# rys_PCB.net
KiCad netlist of a schematic drawn in Altium Designer
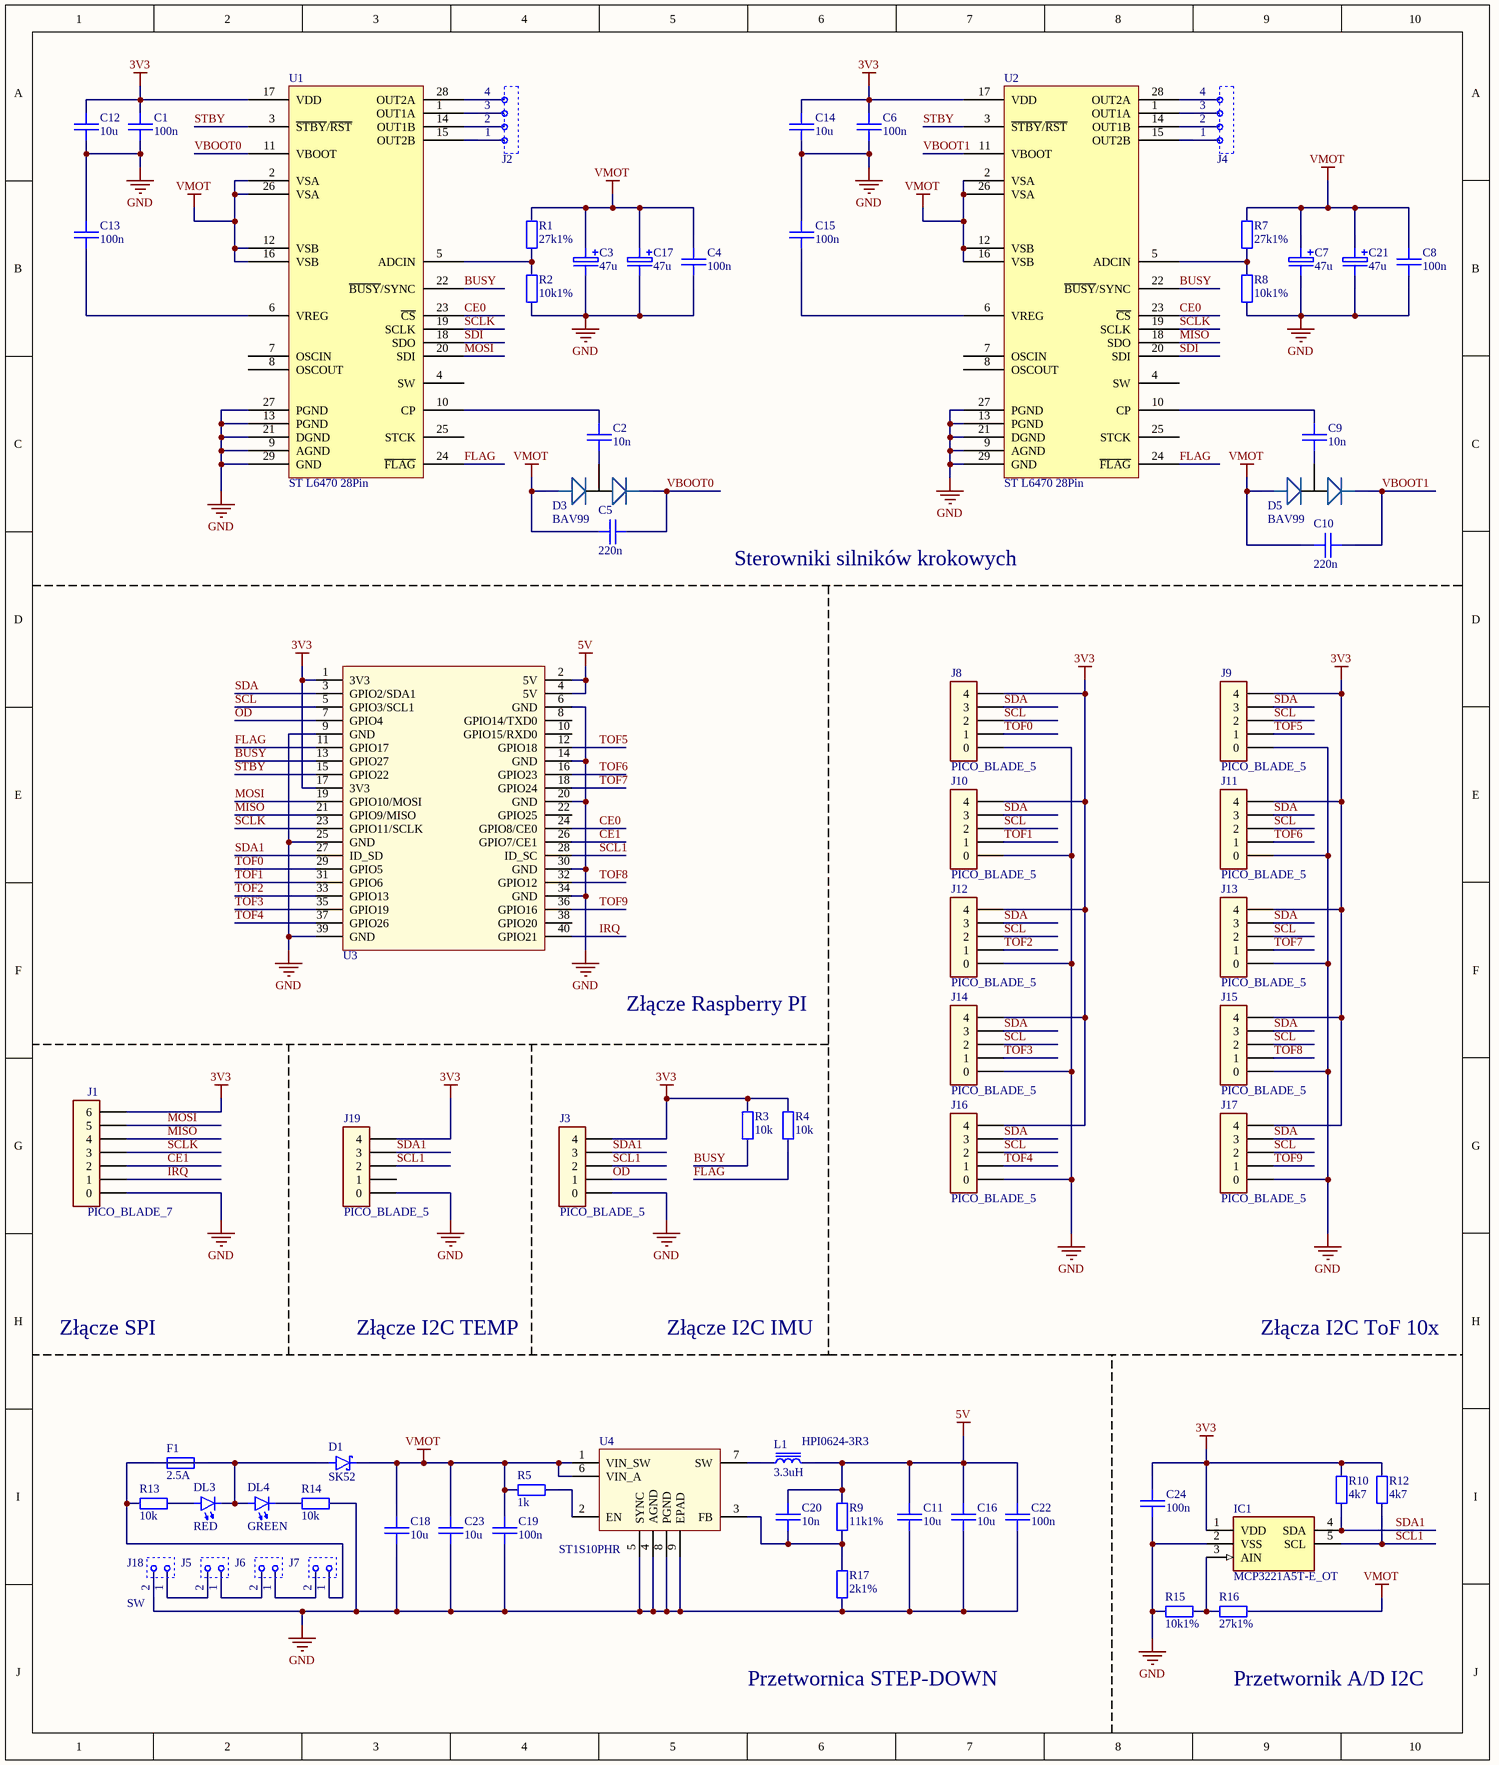
[diagram p0: rys_PCB.SchDoc]

(export (version "E")
  (design (tool "Eeschema 10.0.6"))
  (components
    (comp (ref "C1")
      (value "100n")
      (footprint "Other-Discrete:0603")
      (description "Ceramic Capacitor")
      (libsource (lib "Disc-Other") (part "C_CER"))
    )
    (comp (ref "C2")
      (value "10n")
      (footprint "Other-Discrete:0603")
      (description "Ceramic Capacitor")
      (libsource (lib "Disc-Other") (part "C_CER"))
    )
    (comp (ref "C3")
      (value "47u")
      (footprint "_C_TAN_D")
      (description "Tantalum Capacitor")
      (libsource (lib "Disc-Other") (part "C_TAN"))
    )
    (comp (ref "C4")
      (value "100n")
      (footprint "Other-Discrete:0603")
      (description "Ceramic Capacitor")
      (libsource (lib "Disc-Other") (part "C_CER"))
    )
    (comp (ref "C5")
      (value "220n")
      (footprint "Other-Discrete:0805")
      (description "Ceramic Capacitor")
      (libsource (lib "Disc-Other") (part "C_CER"))
    )
    (comp (ref "C6")
      (value "100n")
      (footprint "Other-Discrete:0603")
      (description "Ceramic Capacitor")
      (libsource (lib "Disc-Other") (part "C_CER"))
    )
    (comp (ref "C7")
      (value "47u")
      (footprint "_C_TAN_D")
      (description "Tantalum Capacitor")
      (libsource (lib "Disc-Other") (part "C_TAN"))
    )
    (comp (ref "C8")
      (value "100n")
      (footprint "Other-Discrete:0603")
      (description "Ceramic Capacitor")
      (libsource (lib "Disc-Other") (part "C_CER"))
    )
    (comp (ref "C9")
      (value "10n")
      (footprint "Other-Discrete:0603")
      (description "Ceramic Capacitor")
      (libsource (lib "Disc-Other") (part "C_CER"))
    )
    (comp (ref "C10")
      (value "220n")
      (footprint "Other-Discrete:0805")
      (description "Ceramic Capacitor")
      (libsource (lib "Disc-Other") (part "C_CER"))
    )
    (comp (ref "C11")
      (value "10u")
      (footprint "Other-Discrete:1210_C")
      (description "Ceramic Capacitor")
      (libsource (lib "Disc-Other") (part "C_CER"))
    )
    (comp (ref "C12")
      (value "10u")
      (footprint "Other-Discrete:1206_C")
      (description "Ceramic Capacitor")
      (libsource (lib "Disc-Other") (part "C_CER"))
    )
    (comp (ref "C13")
      (value "100n")
      (footprint "Other-Discrete:0603")
      (description "Ceramic Capacitor")
      (libsource (lib "Disc-Other") (part "C_CER"))
    )
    (comp (ref "C14")
      (value "10u")
      (footprint "Other-Discrete:1206_C")
      (description "Ceramic Capacitor")
      (libsource (lib "Disc-Other") (part "C_CER"))
    )
    (comp (ref "C15")
      (value "100n")
      (footprint "Other-Discrete:0603")
      (description "Ceramic Capacitor")
      (libsource (lib "Disc-Other") (part "C_CER"))
    )
    (comp (ref "C16")
      (value "10u")
      (footprint "Other-Discrete:1210_C")
      (description "Ceramic Capacitor")
      (libsource (lib "Disc-Other") (part "C_CER"))
    )
    (comp (ref "C17")
      (value "47u")
      (footprint "_C_TAN_D")
      (description "Tantalum Capacitor")
      (libsource (lib "Disc-Other") (part "C_TAN"))
    )
    (comp (ref "C18")
      (value "10u")
      (footprint "Other-Discrete:1210_C")
      (description "Ceramic Capacitor")
      (libsource (lib "Disc-Other") (part "C_CER"))
    )
    (comp (ref "C19")
      (value "100n")
      (footprint "Other-Discrete:0805")
      (description "Ceramic Capacitor")
      (libsource (lib "Disc-Other") (part "C_CER"))
    )
    (comp (ref "C20")
      (value "10n")
      (footprint "Other-Discrete:0603")
      (description "Ceramic Capacitor")
      (libsource (lib "Disc-Other") (part "C_CER"))
    )
    (comp (ref "C21")
      (value "47u")
      (footprint "_C_TAN_D")
      (description "Tantalum Capacitor")
      (libsource (lib "Disc-Other") (part "C_TAN"))
    )
    (comp (ref "C22")
      (value "100n")
      (footprint "Other-Discrete:0805")
      (description "Ceramic Capacitor")
      (libsource (lib "Disc-Other") (part "C_CER"))
    )
    (comp (ref "C23")
      (value "10u")
      (footprint "Other-Discrete:1210_C")
      (description "Ceramic Capacitor")
      (libsource (lib "Disc-Other") (part "C_CER"))
    )
    (comp (ref "C24")
      (value "100n")
      (footprint "Other-Discrete:0603")
      (description "Ceramic Capacitor")
      (libsource (lib "Disc-Other") (part "C_CER"))
    )
    (comp (ref "D1")
      (value "SK52")
      (footprint "SMB/DO-214AA")
      (description "Schottky Diode 2A 60V")
      (libsource (lib "Disc-Diodes") (part "SK26"))
    )
    (comp (ref "D3")
      (value "BAV99")
      (footprint "SOT-23")
      (description "Charge pump diode")
      (libsource (lib "rys_component_lib") (part "BAV99"))
    )
    (comp (ref "D5")
      (value "BAV99")
      (footprint "SOT-23")
      (description "Charge pump diode")
      (libsource (lib "rys_component_lib") (part "BAV99"))
    )
    (comp (ref "DL3")
      (value "RED")
      (footprint "Other-Discrete:0805_LED")
      (description "Light Emitting Diode")
      (libsource (lib "Disc-Opto") (part "LED1"))
    )
    (comp (ref "DL4")
      (value "GREEN")
      (footprint "Other-Discrete:0805_LED")
      (description "Light Emitting Diode")
      (libsource (lib "Disc-Opto") (part "LED1"))
    )
    (comp (ref "F1")
      (value "2.5A")
      (footprint "1206_R")
      (description "Fuse")
      (libsource (lib "rys_component_lib") (part "F"))
    )
    (comp (ref "IC1")
      (value "MCP3221A5T-E_OT")
      (footprint "SamacSys:SOT95P280X145-5N")
      (description "Integrated Circuit")
      (fields
        (field (name "MANUFACTURER_PART_NUMBER") "MCP3221A5T-E/OT")
        (field (name "MOUSER PART NUMBER") "579-MCP3221A5T-E/OT")
      )
      (libsource (lib "*") (part "MCP3221A5T-E_OT"))
    )
    (comp (ref "J1")
      (value "PICO_BLADE_7")
      (footprint "PicoBlade_THT_1x7_HEADER")
      (description "1x7 header")
      (libsource (lib "rys_component_lib") (part "PICO_BLADE_7"))
    )
    (comp (ref "J2")
      (value "Molex Microfit")
      (footprint "MICROFIT 4x1 Vertical")
      (libsource (lib "rys_component_lib") (part "Microfit 1x4"))
    )
    (comp (ref "J3")
      (value "PICO_BLADE_5")
      (footprint "PicoBlade_THT_1x5_HEADER")
      (description "1x5 header")
      (libsource (lib "rys_component_lib") (part "PICO_BLADE_5"))
    )
    (comp (ref "J4")
      (value "Molex Microfit")
      (footprint "MICROFIT 4x1 Vertical")
      (libsource (lib "rys_component_lib") (part "Microfit 1x4"))
    )
    (comp (ref "J5")
      (value "Molex Microfit")
      (footprint "MicroFit:MICROFIT 1x2 Vertical")
      (libsource (lib "Connectors") (part "Microfit 2x1"))
    )
    (comp (ref "J6")
      (value "Molex Microfit")
      (footprint "MicroFit:MICROFIT 1x2 Vertical")
      (libsource (lib "Connectors") (part "Microfit 2x1"))
    )
    (comp (ref "J7")
      (value "Molex Microfit")
      (footprint "MicroFit:MICROFIT 1x2 Vertical")
      (libsource (lib "Connectors") (part "Microfit 2x1"))
    )
    (comp (ref "J8")
      (value "PICO_BLADE_5")
      (footprint "PicoBlade_THT_1x5_HEADER")
      (description "1x5 header")
      (libsource (lib "rys_component_lib") (part "PICO_BLADE_5"))
    )
    (comp (ref "J9")
      (value "PICO_BLADE_5")
      (footprint "PicoBlade_THT_1x5_HEADER")
      (description "1x5 header")
      (libsource (lib "rys_component_lib") (part "PICO_BLADE_5"))
    )
    (comp (ref "J10")
      (value "PICO_BLADE_5")
      (footprint "PicoBlade_THT_1x5_HEADER")
      (description "1x5 header")
      (libsource (lib "rys_component_lib") (part "PICO_BLADE_5"))
    )
    (comp (ref "J11")
      (value "PICO_BLADE_5")
      (footprint "PicoBlade_THT_1x5_HEADER")
      (description "1x5 header")
      (libsource (lib "rys_component_lib") (part "PICO_BLADE_5"))
    )
    (comp (ref "J12")
      (value "PICO_BLADE_5")
      (footprint "PicoBlade_THT_1x5_HEADER")
      (description "1x5 header")
      (libsource (lib "rys_component_lib") (part "PICO_BLADE_5"))
    )
    (comp (ref "J13")
      (value "PICO_BLADE_5")
      (footprint "PicoBlade_THT_1x5_HEADER")
      (description "1x5 header")
      (libsource (lib "rys_component_lib") (part "PICO_BLADE_5"))
    )
    (comp (ref "J14")
      (value "PICO_BLADE_5")
      (footprint "PicoBlade_THT_1x5_HEADER")
      (description "1x5 header")
      (libsource (lib "rys_component_lib") (part "PICO_BLADE_5"))
    )
    (comp (ref "J15")
      (value "PICO_BLADE_5")
      (footprint "PicoBlade_THT_1x5_HEADER")
      (description "1x5 header")
      (libsource (lib "rys_component_lib") (part "PICO_BLADE_5"))
    )
    (comp (ref "J16")
      (value "PICO_BLADE_5")
      (footprint "PicoBlade_THT_1x5_HEADER")
      (description "1x5 header")
      (libsource (lib "rys_component_lib") (part "PICO_BLADE_5"))
    )
    (comp (ref "J17")
      (value "PICO_BLADE_5")
      (footprint "PicoBlade_THT_1x5_HEADER")
      (description "1x5 header")
      (libsource (lib "rys_component_lib") (part "PICO_BLADE_5"))
    )
    (comp (ref "J18")
      (value "Molex Microfit")
      (footprint "MicroFit:MICROFIT 1x2 Vertical")
      (libsource (lib "Connectors") (part "Microfit 2x1"))
    )
    (comp (ref "J19")
      (value "PICO_BLADE_5")
      (footprint "PicoBlade_THT_1x5_HEADER")
      (description "1x5 header")
      (libsource (lib "rys_component_lib") (part "PICO_BLADE_5"))
    )
    (comp (ref "L1")
      (value "3.3uH")
      (footprint "L_HPI0624")
      (description "Inductor")
      (fields (field (name "SYMBOL") "HPI0624-3R3"))
      (libsource (lib "rys_component_lib") (part "L_IND_HPI0624-3R3"))
    )
    (comp (ref "R1")
      (value "27k1%")
      (footprint "Other-Discrete:0603_R")
      (description "Resistor")
      (libsource (lib "Disc-Other") (part "R"))
    )
    (comp (ref "R2")
      (value "10k1%")
      (footprint "Other-Discrete:0603_R")
      (description "Resistor")
      (libsource (lib "Disc-Other") (part "R"))
    )
    (comp (ref "R3")
      (value "10k")
      (footprint "Other-Discrete:0603_R")
      (description "Resistor")
      (libsource (lib "Disc-Other") (part "R"))
    )
    (comp (ref "R4")
      (value "10k")
      (footprint "Other-Discrete:0603_R")
      (description "Resistor")
      (libsource (lib "Disc-Other") (part "R"))
    )
    (comp (ref "R5")
      (value "1k")
      (footprint "Other-Discrete:0603_R")
      (description "Resistor")
      (libsource (lib "Disc-Other") (part "R"))
    )
    (comp (ref "R7")
      (value "27k1%")
      (footprint "Other-Discrete:0603_R")
      (description "Resistor")
      (libsource (lib "Disc-Other") (part "R"))
    )
    (comp (ref "R8")
      (value "10k1%")
      (footprint "Other-Discrete:0603_R")
      (description "Resistor")
      (libsource (lib "Disc-Other") (part "R"))
    )
    (comp (ref "R9")
      (value "11k1%")
      (footprint "Other-Discrete:0603_R")
      (description "Resistor")
      (libsource (lib "Disc-Other") (part "R"))
    )
    (comp (ref "R10")
      (value "4k7")
      (footprint "Other-Discrete:0603_R")
      (description "Resistor")
      (libsource (lib "Disc-Other") (part "R"))
    )
    (comp (ref "R12")
      (value "4k7")
      (footprint "Other-Discrete:0603_R")
      (description "Resistor")
      (libsource (lib "Disc-Other") (part "R"))
    )
    (comp (ref "R13")
      (value "10k")
      (footprint "Other-Discrete:0603_R")
      (description "Resistor")
      (libsource (lib "Disc-Other") (part "R"))
    )
    (comp (ref "R14")
      (value "10k")
      (footprint "Other-Discrete:0603_R")
      (description "Resistor")
      (libsource (lib "Disc-Other") (part "R"))
    )
    (comp (ref "R15")
      (value "10k1%")
      (footprint "Other-Discrete:0603_R")
      (description "Resistor")
      (libsource (lib "Disc-Other") (part "R"))
    )
    (comp (ref "R16")
      (value "27k1%")
      (footprint "Other-Discrete:0603_R")
      (description "Resistor")
      (libsource (lib "Disc-Other") (part "R"))
    )
    (comp (ref "R17")
      (value "2k1%")
      (footprint "Other-Discrete:0603_R")
      (description "Resistor")
      (libsource (lib "Disc-Other") (part "R"))
    )
    (comp (ref "U1")
      (value "ST L6470 28Pin")
      (footprint "ST HTSSOP-28")
      (description "SPI stepper driver")
      (libsource (lib "rys_component_lib") (part "ST L6470 28Pin"))
    )
    (comp (ref "U2")
      (value "ST L6470 28Pin")
      (footprint "ST HTSSOP-28")
      (description "SPI stepper driver")
      (libsource (lib "rys_component_lib") (part "ST L6470 28Pin"))
    )
    (comp (ref "U3")
      (value "RaspberryPi_3B+")
      (footprint "RaspberryPi_S")
      (libsource (lib "rys_component_lib") (part "RaspberryPi_3B+"))
    )
    (comp (ref "U4")
      (value "ST1S10PHR")
      (footprint "HSOP8")
      (description "DC/DC converter 3A")
      (libsource (lib "rys_component_lib") (part "ST1S10PHR"))
    )
  )
  (nets
    (net (code "1") (name "/BUSY") (class "Default")
      (node (ref "R3") (pin "1") (pinfunction "1_1") (pintype "passive"))
      (node (ref "U1") (pin "22") (pinfunction "~{BUSY}/SYNC_22") (pintype "passive"))
      (node (ref "U2") (pin "22") (pinfunction "~{BUSY}/SYNC_22") (pintype "passive"))
      (node (ref "U3") (pin "13") (pinfunction "GPIO27_13") (pintype "passive"))
    )
    (net (code "2") (name "/CE0") (class "Default")
      (node (ref "U1") (pin "23") (pinfunction "~{CS}_23") (pintype "passive"))
      (node (ref "U2") (pin "23") (pinfunction "~{CS}_23") (pintype "passive"))
      (node (ref "U3") (pin "24") (pinfunction "GPIO8/CE0_24") (pintype "passive"))
    )
    (net (code "3") (name "/CE1") (class "Default")
      (node (ref "J1") (pin "2") (pinfunction "2_2") (pintype "passive"))
      (node (ref "U3") (pin "26") (pinfunction "GPIO7/CE1_26") (pintype "passive"))
    )
    (net (code "4") (name "/FLAG") (class "Default")
      (node (ref "R4") (pin "1") (pinfunction "1_1") (pintype "passive"))
      (node (ref "U1") (pin "24") (pinfunction "~{FLAG}_24") (pintype "passive"))
      (node (ref "U2") (pin "24") (pinfunction "~{FLAG}_24") (pintype "passive"))
      (node (ref "U3") (pin "11") (pinfunction "GPIO17_11") (pintype "passive"))
    )
    (net (code "5") (name "/IRQ") (class "Default")
      (node (ref "J1") (pin "1") (pinfunction "1_1") (pintype "passive"))
      (node (ref "U3") (pin "40") (pinfunction "GPIO21_40") (pintype "passive"))
    )
    (net (code "6") (name "/MISO") (class "Default")
      (node (ref "J1") (pin "4") (pinfunction "4_4") (pintype "passive"))
      (node (ref "U2") (pin "18") (pinfunction "SDO_18") (pintype "passive"))
      (node (ref "U3") (pin "21") (pinfunction "GPIO9/MISO_21") (pintype "passive"))
    )
    (net (code "7") (name "/MOSI") (class "Default")
      (node (ref "J1") (pin "5") (pinfunction "5_5") (pintype "passive"))
      (node (ref "U1") (pin "20") (pinfunction "SDI_20") (pintype "passive"))
      (node (ref "U3") (pin "19") (pinfunction "GPIO10/MOSI_19") (pintype "passive"))
    )
    (net (code "8") (name "/O~{D}") (class "Default")
      (node (ref "J3") (pin "1") (pinfunction "1_1") (pintype "passive"))
      (node (ref "U3") (pin "7") (pinfunction "GPIO4_7") (pintype "passive"))
    )
    (net (code "9") (name "/SCL") (class "Default")
      (node (ref "J10") (pin "2") (pinfunction "2_2") (pintype "passive"))
      (node (ref "J11") (pin "2") (pinfunction "2_2") (pintype "passive"))
      (node (ref "J12") (pin "2") (pinfunction "2_2") (pintype "passive"))
      (node (ref "J13") (pin "2") (pinfunction "2_2") (pintype "passive"))
      (node (ref "J14") (pin "2") (pinfunction "2_2") (pintype "passive"))
      (node (ref "J15") (pin "2") (pinfunction "2_2") (pintype "passive"))
      (node (ref "J16") (pin "2") (pinfunction "2_2") (pintype "passive"))
      (node (ref "J17") (pin "2") (pinfunction "2_2") (pintype "passive"))
      (node (ref "J8") (pin "2") (pinfunction "2_2") (pintype "passive"))
      (node (ref "J9") (pin "2") (pinfunction "2_2") (pintype "passive"))
      (node (ref "U3") (pin "5") (pinfunction "GPIO3/SCL1_5") (pintype "passive"))
    )
    (net (code "10") (name "/SCL1") (class "Default")
      (node (ref "IC1") (pin "5") (pinfunction "SCL_5") (pintype "passive"))
      (node (ref "J19") (pin "2") (pinfunction "2_2") (pintype "passive"))
      (node (ref "J3") (pin "2") (pinfunction "2_2") (pintype "passive"))
      (node (ref "R12") (pin "1") (pinfunction "1_1") (pintype "passive"))
      (node (ref "U3") (pin "28") (pinfunction "ID_SC_28") (pintype "passive"))
    )
    (net (code "11") (name "/SCLK") (class "Default")
      (node (ref "J1") (pin "3") (pinfunction "3_3") (pintype "passive"))
      (node (ref "U1") (pin "19") (pinfunction "SCLK_19") (pintype "passive"))
      (node (ref "U2") (pin "19") (pinfunction "SCLK_19") (pintype "passive"))
      (node (ref "U3") (pin "23") (pinfunction "GPIO11/SCLK_23") (pintype "passive"))
    )
    (net (code "12") (name "/SDA") (class "Default")
      (node (ref "J10") (pin "3") (pinfunction "3_3") (pintype "passive"))
      (node (ref "J11") (pin "3") (pinfunction "3_3") (pintype "passive"))
      (node (ref "J12") (pin "3") (pinfunction "3_3") (pintype "passive"))
      (node (ref "J13") (pin "3") (pinfunction "3_3") (pintype "passive"))
      (node (ref "J14") (pin "3") (pinfunction "3_3") (pintype "passive"))
      (node (ref "J15") (pin "3") (pinfunction "3_3") (pintype "passive"))
      (node (ref "J16") (pin "3") (pinfunction "3_3") (pintype "passive"))
      (node (ref "J17") (pin "3") (pinfunction "3_3") (pintype "passive"))
      (node (ref "J8") (pin "3") (pinfunction "3_3") (pintype "passive"))
      (node (ref "J9") (pin "3") (pinfunction "3_3") (pintype "passive"))
      (node (ref "U3") (pin "3") (pinfunction "GPIO2/SDA1_3") (pintype "passive"))
    )
    (net (code "13") (name "/SDA1") (class "Default")
      (node (ref "IC1") (pin "4") (pinfunction "SDA_4") (pintype "passive"))
      (node (ref "J19") (pin "3") (pinfunction "3_3") (pintype "passive"))
      (node (ref "J3") (pin "3") (pinfunction "3_3") (pintype "passive"))
      (node (ref "R10") (pin "1") (pinfunction "1_1") (pintype "passive"))
      (node (ref "U3") (pin "27") (pinfunction "ID_SD_27") (pintype "passive"))
    )
    (net (code "14") (name "/SDI") (class "Default")
      (node (ref "U1") (pin "18") (pinfunction "SDO_18") (pintype "passive"))
      (node (ref "U2") (pin "20") (pinfunction "SDI_20") (pintype "passive"))
    )
    (net (code "15") (name "/STBY") (class "Default")
      (node (ref "U1") (pin "3") (pinfunction "~{STBY}/~{RST}_3") (pintype "passive"))
      (node (ref "U2") (pin "3") (pinfunction "~{STBY}/~{RST}_3") (pintype "passive"))
      (node (ref "U3") (pin "15") (pinfunction "GPIO22_15") (pintype "passive"))
    )
    (net (code "16") (name "/TOF0") (class "Default")
      (node (ref "J8") (pin "1") (pinfunction "1_1") (pintype "passive"))
      (node (ref "U3") (pin "29") (pinfunction "GPIO5_29") (pintype "passive"))
    )
    (net (code "17") (name "/TOF1") (class "Default")
      (node (ref "J10") (pin "1") (pinfunction "1_1") (pintype "passive"))
      (node (ref "U3") (pin "31") (pinfunction "GPIO6_31") (pintype "passive"))
    )
    (net (code "18") (name "/TOF2") (class "Default")
      (node (ref "J12") (pin "1") (pinfunction "1_1") (pintype "passive"))
      (node (ref "U3") (pin "33") (pinfunction "GPIO13_33") (pintype "passive"))
    )
    (net (code "19") (name "/TOF3") (class "Default")
      (node (ref "J14") (pin "1") (pinfunction "1_1") (pintype "passive"))
      (node (ref "U3") (pin "35") (pinfunction "GPIO19_35") (pintype "passive"))
    )
    (net (code "20") (name "/TOF4") (class "Default")
      (node (ref "J16") (pin "1") (pinfunction "1_1") (pintype "passive"))
      (node (ref "U3") (pin "37") (pinfunction "GPIO26_37") (pintype "passive"))
    )
    (net (code "21") (name "/TOF5") (class "Default")
      (node (ref "J9") (pin "1") (pinfunction "1_1") (pintype "passive"))
      (node (ref "U3") (pin "12") (pinfunction "GPIO18_12") (pintype "passive"))
    )
    (net (code "22") (name "/TOF6") (class "Default")
      (node (ref "J11") (pin "1") (pinfunction "1_1") (pintype "passive"))
      (node (ref "U3") (pin "16") (pinfunction "GPIO23_16") (pintype "passive"))
    )
    (net (code "23") (name "/TOF7") (class "Default")
      (node (ref "J13") (pin "1") (pinfunction "1_1") (pintype "passive"))
      (node (ref "U3") (pin "18") (pinfunction "GPIO24_18") (pintype "passive"))
    )
    (net (code "24") (name "/TOF8") (class "Default")
      (node (ref "J15") (pin "1") (pinfunction "1_1") (pintype "passive"))
      (node (ref "U3") (pin "32") (pinfunction "GPIO12_32") (pintype "passive"))
    )
    (net (code "25") (name "/TOF9") (class "Default")
      (node (ref "J17") (pin "1") (pinfunction "1_1") (pintype "passive"))
      (node (ref "U3") (pin "36") (pinfunction "GPIO16_36") (pintype "passive"))
    )
    (net (code "26") (name "/VBOOT0") (class "Default")
      (node (ref "C5") (pin "1") (pinfunction "1_1") (pintype "passive"))
      (node (ref "D3") (pin "2") (pinfunction "2_2") (pintype "passive"))
      (node (ref "U1") (pin "11") (pinfunction "VBOOT_11") (pintype "passive"))
    )
    (net (code "27") (name "/VBOOT1") (class "Default")
      (node (ref "C10") (pin "1") (pinfunction "1_1") (pintype "passive"))
      (node (ref "D5") (pin "2") (pinfunction "2_2") (pintype "passive"))
      (node (ref "U2") (pin "11") (pinfunction "VBOOT_11") (pintype "passive"))
    )
    (net (code "28") (name "3V3") (class "Default")
      (node (ref "C1") (pin "2") (pinfunction "2_2") (pintype "passive"))
      (node (ref "C12") (pin "2") (pinfunction "2_2") (pintype "passive"))
      (node (ref "C14") (pin "2") (pinfunction "2_2") (pintype "passive"))
      (node (ref "C24") (pin "2") (pinfunction "2_2") (pintype "passive"))
      (node (ref "C6") (pin "2") (pinfunction "2_2") (pintype "passive"))
      (node (ref "IC1") (pin "1") (pinfunction "VDD_1") (pintype "power_in"))
      (node (ref "J1") (pin "6") (pinfunction "6_6") (pintype "passive"))
      (node (ref "J10") (pin "4") (pinfunction "4_4") (pintype "passive"))
      (node (ref "J11") (pin "4") (pinfunction "4_4") (pintype "passive"))
      (node (ref "J12") (pin "4") (pinfunction "4_4") (pintype "passive"))
      (node (ref "J13") (pin "4") (pinfunction "4_4") (pintype "passive"))
      (node (ref "J14") (pin "4") (pinfunction "4_4") (pintype "passive"))
      (node (ref "J15") (pin "4") (pinfunction "4_4") (pintype "passive"))
      (node (ref "J16") (pin "4") (pinfunction "4_4") (pintype "passive"))
      (node (ref "J17") (pin "4") (pinfunction "4_4") (pintype "passive"))
      (node (ref "J19") (pin "4") (pinfunction "4_4") (pintype "passive"))
      (node (ref "J3") (pin "4") (pinfunction "4_4") (pintype "passive"))
      (node (ref "J8") (pin "4") (pinfunction "4_4") (pintype "passive"))
      (node (ref "J9") (pin "4") (pinfunction "4_4") (pintype "passive"))
      (node (ref "R10") (pin "2") (pinfunction "2_2") (pintype "passive"))
      (node (ref "R12") (pin "2") (pinfunction "2_2") (pintype "passive"))
      (node (ref "R3") (pin "2") (pinfunction "2_2") (pintype "passive"))
      (node (ref "R4") (pin "2") (pinfunction "2_2") (pintype "passive"))
      (node (ref "U1") (pin "17") (pinfunction "VDD_17") (pintype "passive"))
      (node (ref "U2") (pin "17") (pinfunction "VDD_17") (pintype "passive"))
      (node (ref "U3") (pin "1") (pinfunction "3V3_1") (pintype "passive"))
      (node (ref "U3") (pin "17") (pinfunction "3V3_17") (pintype "passive"))
    )
    (net (code "29") (name "5V") (class "Default")
      (node (ref "C11") (pin "2") (pinfunction "2_2") (pintype "passive"))
      (node (ref "C16") (pin "2") (pinfunction "2_2") (pintype "passive"))
      (node (ref "C20") (pin "2") (pinfunction "2_2") (pintype "passive"))
      (node (ref "C22") (pin "2") (pinfunction "2_2") (pintype "passive"))
      (node (ref "L1") (pin "1") (pinfunction "1_1") (pintype "passive"))
      (node (ref "R9") (pin "2") (pinfunction "2_2") (pintype "passive"))
      (node (ref "U3") (pin "2") (pinfunction "5V_2") (pintype "passive"))
      (node (ref "U3") (pin "4") (pinfunction "5V_4") (pintype "passive"))
    )
    (net (code "30") (name "GND") (class "Default")
      (node (ref "C1") (pin "1") (pinfunction "1_1") (pintype "passive"))
      (node (ref "C11") (pin "1") (pinfunction "1_1") (pintype "passive"))
      (node (ref "C12") (pin "1") (pinfunction "1_1") (pintype "passive"))
      (node (ref "C13") (pin "2") (pinfunction "2_2") (pintype "passive"))
      (node (ref "C14") (pin "1") (pinfunction "1_1") (pintype "passive"))
      (node (ref "C15") (pin "2") (pinfunction "2_2") (pintype "passive"))
      (node (ref "C16") (pin "1") (pinfunction "1_1") (pintype "passive"))
      (node (ref "C17") (pin "N") (pinfunction "2_N") (pintype "passive"))
      (node (ref "C18") (pin "1") (pinfunction "1_1") (pintype "passive"))
      (node (ref "C19") (pin "1") (pinfunction "1_1") (pintype "passive"))
      (node (ref "C21") (pin "N") (pinfunction "2_N") (pintype "passive"))
      (node (ref "C22") (pin "1") (pinfunction "1_1") (pintype "passive"))
      (node (ref "C23") (pin "1") (pinfunction "1_1") (pintype "passive"))
      (node (ref "C24") (pin "1") (pinfunction "1_1") (pintype "passive"))
      (node (ref "C3") (pin "N") (pinfunction "2_N") (pintype "passive"))
      (node (ref "C4") (pin "2") (pinfunction "2_2") (pintype "passive"))
      (node (ref "C6") (pin "1") (pinfunction "1_1") (pintype "passive"))
      (node (ref "C7") (pin "N") (pinfunction "2_N") (pintype "passive"))
      (node (ref "C8") (pin "2") (pinfunction "2_2") (pintype "passive"))
      (node (ref "IC1") (pin "2") (pinfunction "VSS_2") (pintype "power_in"))
      (node (ref "J1") (pin "0") (pinfunction "0_0") (pintype "passive"))
      (node (ref "J10") (pin "0") (pinfunction "0_0") (pintype "passive"))
      (node (ref "J11") (pin "0") (pinfunction "0_0") (pintype "passive"))
      (node (ref "J12") (pin "0") (pinfunction "0_0") (pintype "passive"))
      (node (ref "J13") (pin "0") (pinfunction "0_0") (pintype "passive"))
      (node (ref "J14") (pin "0") (pinfunction "0_0") (pintype "passive"))
      (node (ref "J15") (pin "0") (pinfunction "0_0") (pintype "passive"))
      (node (ref "J16") (pin "0") (pinfunction "0_0") (pintype "passive"))
      (node (ref "J17") (pin "0") (pinfunction "0_0") (pintype "passive"))
      (node (ref "J18") (pin "2") (pintype "passive"))
      (node (ref "J19") (pin "0") (pinfunction "0_0") (pintype "passive"))
      (node (ref "J3") (pin "0") (pinfunction "0_0") (pintype "passive"))
      (node (ref "J8") (pin "0") (pinfunction "0_0") (pintype "passive"))
      (node (ref "J9") (pin "0") (pinfunction "0_0") (pintype "passive"))
      (node (ref "R14") (pin "1") (pinfunction "1_1") (pintype "passive"))
      (node (ref "R15") (pin "1") (pinfunction "1_1") (pintype "passive"))
      (node (ref "R17") (pin "1") (pinfunction "1_1") (pintype "passive"))
      (node (ref "R2") (pin "1") (pinfunction "1_1") (pintype "passive"))
      (node (ref "R8") (pin "1") (pinfunction "1_1") (pintype "passive"))
      (node (ref "U1") (pin "13") (pinfunction "PGND_13") (pintype "passive"))
      (node (ref "U1") (pin "21") (pinfunction "DGND_21") (pintype "passive"))
      (node (ref "U1") (pin "27") (pinfunction "PGND_27") (pintype "passive"))
      (node (ref "U1") (pin "29") (pinfunction "GND_29") (pintype "passive"))
      (node (ref "U1") (pin "9") (pinfunction "AGND_9") (pintype "passive"))
      (node (ref "U2") (pin "13") (pinfunction "PGND_13") (pintype "passive"))
      (node (ref "U2") (pin "21") (pinfunction "DGND_21") (pintype "passive"))
      (node (ref "U2") (pin "27") (pinfunction "PGND_27") (pintype "passive"))
      (node (ref "U2") (pin "29") (pinfunction "GND_29") (pintype "passive"))
      (node (ref "U2") (pin "9") (pinfunction "AGND_9") (pintype "passive"))
      (node (ref "U3") (pin "14") (pinfunction "GND_14") (pintype "passive"))
      (node (ref "U3") (pin "20") (pinfunction "GND_20") (pintype "passive"))
      (node (ref "U3") (pin "25") (pinfunction "GND_25") (pintype "passive"))
      (node (ref "U3") (pin "30") (pinfunction "GND_30") (pintype "passive"))
      (node (ref "U3") (pin "34") (pinfunction "GND_34") (pintype "passive"))
      (node (ref "U3") (pin "39") (pinfunction "GND_39") (pintype "passive"))
      (node (ref "U3") (pin "6") (pinfunction "GND_6") (pintype "passive"))
      (node (ref "U3") (pin "9") (pinfunction "GND_9") (pintype "passive"))
      (node (ref "U4") (pin "4") (pinfunction "AGND_4") (pintype "passive"))
      (node (ref "U4") (pin "5") (pinfunction "SYNC_5") (pintype "passive"))
      (node (ref "U4") (pin "8") (pinfunction "PGND_8") (pintype "passive"))
      (node (ref "U4") (pin "9") (pinfunction "EPAD_9") (pintype "passive"))
    )
    (net (code "31") (name "Net-(C2-Pad1)") (class "Default")
      (node (ref "C2") (pin "1") (pinfunction "1_1") (pintype "passive"))
      (node (ref "D3") (pin "3") (pinfunction "3_3") (pintype "passive"))
    )
    (net (code "32") (name "Net-(C9-Pad1)") (class "Default")
      (node (ref "C9") (pin "1") (pinfunction "1_1") (pintype "passive"))
      (node (ref "D5") (pin "3") (pinfunction "3_3") (pintype "passive"))
    )
    (net (code "33") (name "Net-(D1-2)") (class "Default")
      (node (ref "D1") (pin "A") (pinfunction "2_A") (pintype "passive"))
      (node (ref "DL3") (pin "K") (pinfunction "1_K") (pintype "passive"))
      (node (ref "DL4") (pin "A") (pinfunction "2_A") (pintype "passive"))
      (node (ref "F1") (pin "1") (pinfunction "1_1") (pintype "passive"))
    )
    (net (code "34") (name "Net-(DL3-2)") (class "Default")
      (node (ref "DL3") (pin "A") (pinfunction "2_A") (pintype "passive"))
      (node (ref "R13") (pin "1") (pinfunction "1_1") (pintype "passive"))
    )
    (net (code "35") (name "Net-(DL4-1)") (class "Default")
      (node (ref "DL4") (pin "K") (pinfunction "1_K") (pintype "passive"))
      (node (ref "R14") (pin "2") (pinfunction "2_2") (pintype "passive"))
    )
    (net (code "36") (name "Net-(F1-Pad2)") (class "Default")
      (node (ref "F1") (pin "2") (pinfunction "2_2") (pintype "passive"))
      (node (ref "J7") (pin "1") (pintype "passive"))
      (node (ref "R13") (pin "2") (pinfunction "2_2") (pintype "passive"))
    )
    (net (code "37") (name "Net-(IC1-AIN)") (class "Default")
      (node (ref "IC1") (pin "3") (pinfunction "AIN_3") (pintype "input"))
      (node (ref "R15") (pin "2") (pinfunction "2_2") (pintype "passive"))
      (node (ref "R16") (pin "1") (pinfunction "1_1") (pintype "passive"))
    )
    (net (code "38") (name "Net-(J5-Pad1)") (class "Default")
      (node (ref "J5") (pin "1") (pintype "passive"))
      (node (ref "J6") (pin "2") (pintype "passive"))
    )
    (net (code "39") (name "Net-(J6-Pad1)") (class "Default")
      (node (ref "J6") (pin "1") (pintype "passive"))
      (node (ref "J7") (pin "2") (pintype "passive"))
    )
    (net (code "40") (name "Net-(J18-Pad1)") (class "Default")
      (node (ref "J18") (pin "1") (pintype "passive"))
      (node (ref "J5") (pin "2") (pintype "passive"))
    )
    (net (code "41") (name "Net-(U1-ADCIN)") (class "Default")
      (node (ref "R1") (pin "1") (pinfunction "1_1") (pintype "passive"))
      (node (ref "R2") (pin "2") (pinfunction "2_2") (pintype "passive"))
      (node (ref "U1") (pin "5") (pinfunction "ADCIN_5") (pintype "passive"))
    )
    (net (code "42") (name "Net-(U1-CP)") (class "Default")
      (node (ref "C2") (pin "2") (pinfunction "2_2") (pintype "passive"))
      (node (ref "U1") (pin "10") (pinfunction "CP_10") (pintype "passive"))
    )
    (net (code "43") (name "Net-(U1-OUT1A)") (class "Default")
      (node (ref "J2") (pin "3") (pintype "passive"))
      (node (ref "U1") (pin "1") (pinfunction "OUT1A_1") (pintype "passive"))
    )
    (net (code "44") (name "Net-(U1-OUT1B)") (class "Default")
      (node (ref "J2") (pin "2") (pintype "passive"))
      (node (ref "U1") (pin "14") (pinfunction "OUT1B_14") (pintype "passive"))
    )
    (net (code "45") (name "Net-(U1-OUT2A)") (class "Default")
      (node (ref "J2") (pin "4") (pintype "passive"))
      (node (ref "U1") (pin "28") (pinfunction "OUT2A_28") (pintype "passive"))
    )
    (net (code "46") (name "Net-(U1-OUT2B)") (class "Default")
      (node (ref "J2") (pin "1") (pintype "passive"))
      (node (ref "U1") (pin "15") (pinfunction "OUT2B_15") (pintype "passive"))
    )
    (net (code "47") (name "Net-(U1-VREG)") (class "Default")
      (node (ref "C13") (pin "1") (pinfunction "1_1") (pintype "passive"))
      (node (ref "U1") (pin "6") (pinfunction "VREG_6") (pintype "passive"))
    )
    (net (code "48") (name "Net-(U2-ADCIN)") (class "Default")
      (node (ref "R7") (pin "1") (pinfunction "1_1") (pintype "passive"))
      (node (ref "R8") (pin "2") (pinfunction "2_2") (pintype "passive"))
      (node (ref "U2") (pin "5") (pinfunction "ADCIN_5") (pintype "passive"))
    )
    (net (code "49") (name "Net-(U2-CP)") (class "Default")
      (node (ref "C9") (pin "2") (pinfunction "2_2") (pintype "passive"))
      (node (ref "U2") (pin "10") (pinfunction "CP_10") (pintype "passive"))
    )
    (net (code "50") (name "Net-(U2-OUT1A)") (class "Default")
      (node (ref "J4") (pin "3") (pintype "passive"))
      (node (ref "U2") (pin "1") (pinfunction "OUT1A_1") (pintype "passive"))
    )
    (net (code "51") (name "Net-(U2-OUT1B)") (class "Default")
      (node (ref "J4") (pin "2") (pintype "passive"))
      (node (ref "U2") (pin "14") (pinfunction "OUT1B_14") (pintype "passive"))
    )
    (net (code "52") (name "Net-(U2-OUT2A)") (class "Default")
      (node (ref "J4") (pin "4") (pintype "passive"))
      (node (ref "U2") (pin "28") (pinfunction "OUT2A_28") (pintype "passive"))
    )
    (net (code "53") (name "Net-(U2-OUT2B)") (class "Default")
      (node (ref "J4") (pin "1") (pintype "passive"))
      (node (ref "U2") (pin "15") (pinfunction "OUT2B_15") (pintype "passive"))
    )
    (net (code "54") (name "Net-(U2-VREG)") (class "Default")
      (node (ref "C15") (pin "1") (pinfunction "1_1") (pintype "passive"))
      (node (ref "U2") (pin "6") (pinfunction "VREG_6") (pintype "passive"))
    )
    (net (code "55") (name "Net-(U4-EN)") (class "Default")
      (node (ref "R5") (pin "1") (pinfunction "1_1") (pintype "passive"))
      (node (ref "U4") (pin "2") (pinfunction "EN_2") (pintype "passive"))
    )
    (net (code "56") (name "Net-(U4-FB)") (class "Default")
      (node (ref "C20") (pin "1") (pinfunction "1_1") (pintype "passive"))
      (node (ref "R17") (pin "2") (pinfunction "2_2") (pintype "passive"))
      (node (ref "R9") (pin "1") (pinfunction "1_1") (pintype "passive"))
      (node (ref "U4") (pin "3") (pinfunction "FB_3") (pintype "passive"))
    )
    (net (code "57") (name "Net-(U4-SW)") (class "Default")
      (node (ref "L1") (pin "2") (pinfunction "2_2") (pintype "passive"))
      (node (ref "U4") (pin "7") (pinfunction "SW_7") (pintype "passive"))
    )
    (net (code "58") (name "VMOT") (class "Default")
      (node (ref "C10") (pin "2") (pinfunction "2_2") (pintype "passive"))
      (node (ref "C17") (pin "P") (pinfunction "1_P") (pintype "passive"))
      (node (ref "C18") (pin "2") (pinfunction "2_2") (pintype "passive"))
      (node (ref "C19") (pin "2") (pinfunction "2_2") (pintype "passive"))
      (node (ref "C21") (pin "P") (pinfunction "1_P") (pintype "passive"))
      (node (ref "C23") (pin "2") (pinfunction "2_2") (pintype "passive"))
      (node (ref "C3") (pin "P") (pinfunction "1_P") (pintype "passive"))
      (node (ref "C4") (pin "1") (pinfunction "1_1") (pintype "passive"))
      (node (ref "C5") (pin "2") (pinfunction "2_2") (pintype "passive"))
      (node (ref "C7") (pin "P") (pinfunction "1_P") (pintype "passive"))
      (node (ref "C8") (pin "1") (pinfunction "1_1") (pintype "passive"))
      (node (ref "D1") (pin "K") (pinfunction "1_K") (pintype "passive"))
      (node (ref "D3") (pin "1") (pinfunction "1_1") (pintype "passive"))
      (node (ref "D5") (pin "1") (pinfunction "1_1") (pintype "passive"))
      (node (ref "R1") (pin "2") (pinfunction "2_2") (pintype "passive"))
      (node (ref "R16") (pin "2") (pinfunction "2_2") (pintype "passive"))
      (node (ref "R5") (pin "2") (pinfunction "2_2") (pintype "passive"))
      (node (ref "R7") (pin "2") (pinfunction "2_2") (pintype "passive"))
      (node (ref "U1") (pin "12") (pinfunction "VSB_12") (pintype "passive"))
      (node (ref "U1") (pin "16") (pinfunction "VSB_16") (pintype "passive"))
      (node (ref "U1") (pin "2") (pinfunction "VSA_2") (pintype "passive"))
      (node (ref "U1") (pin "26") (pinfunction "VSA_26") (pintype "passive"))
      (node (ref "U2") (pin "12") (pinfunction "VSB_12") (pintype "passive"))
      (node (ref "U2") (pin "16") (pinfunction "VSB_16") (pintype "passive"))
      (node (ref "U2") (pin "2") (pinfunction "VSA_2") (pintype "passive"))
      (node (ref "U2") (pin "26") (pinfunction "VSA_26") (pintype "passive"))
      (node (ref "U4") (pin "1") (pinfunction "VIN_SW_1") (pintype "passive"))
      (node (ref "U4") (pin "6") (pinfunction "VIN_A_6") (pintype "passive"))
    )
    (net (code "59") (name "unconnected-(J19-Pad1)") (class "Default")
      (node (ref "J19") (pin "1") (pinfunction "1_1") (pintype "passive"))
    )
    (net (code "60") (name "unconnected-(U1-OSCIN-Pad7)") (class "Default")
      (node (ref "U1") (pin "7") (pinfunction "OSCIN_7") (pintype "passive"))
    )
    (net (code "61") (name "unconnected-(U1-OSCOUT-Pad8)") (class "Default")
      (node (ref "U1") (pin "8") (pinfunction "OSCOUT_8") (pintype "passive"))
    )
    (net (code "62") (name "unconnected-(U1-STCK-Pad25)") (class "Default")
      (node (ref "U1") (pin "25") (pinfunction "STCK_25") (pintype "passive"))
    )
    (net (code "63") (name "unconnected-(U1-SW-Pad4)") (class "Default")
      (node (ref "U1") (pin "4") (pinfunction "SW_4") (pintype "passive"))
    )
    (net (code "64") (name "unconnected-(U2-OSCIN-Pad7)") (class "Default")
      (node (ref "U2") (pin "7") (pinfunction "OSCIN_7") (pintype "passive"))
    )
    (net (code "65") (name "unconnected-(U2-OSCOUT-Pad8)") (class "Default")
      (node (ref "U2") (pin "8") (pinfunction "OSCOUT_8") (pintype "passive"))
    )
    (net (code "66") (name "unconnected-(U2-STCK-Pad25)") (class "Default")
      (node (ref "U2") (pin "25") (pinfunction "STCK_25") (pintype "passive"))
    )
    (net (code "67") (name "unconnected-(U2-SW-Pad4)") (class "Default")
      (node (ref "U2") (pin "4") (pinfunction "SW_4") (pintype "passive"))
    )
    (net (code "68") (name "unconnected-(U3-GPIO14{slash}TXD0-Pad8)") (class "Default")
      (node (ref "U3") (pin "8") (pinfunction "GPIO14/TXD0_8") (pintype "passive"))
    )
    (net (code "69") (name "unconnected-(U3-GPIO15{slash}RXD0-Pad10)") (class "Default")
      (node (ref "U3") (pin "10") (pinfunction "GPIO15/RXD0_10") (pintype "passive"))
    )
    (net (code "70") (name "unconnected-(U3-GPIO20-Pad38)") (class "Default")
      (node (ref "U3") (pin "38") (pinfunction "GPIO20_38") (pintype "passive"))
    )
    (net (code "71") (name "unconnected-(U3-GPIO25-Pad22)") (class "Default")
      (node (ref "U3") (pin "22") (pinfunction "GPIO25_22") (pintype "passive"))
    )
  )
)
